# CAN.net
KiCad netlist of a schematic drawn in Altium Designer
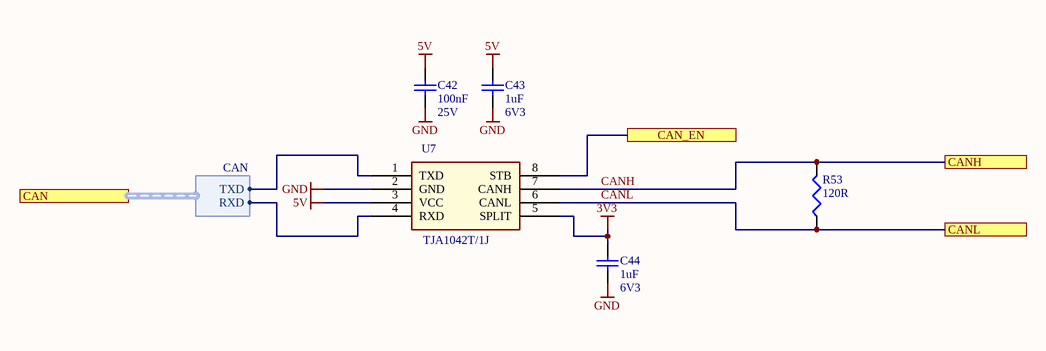
[diagram p0: CAN.SchDoc]

(export (version "E")
  (design (tool "Eeschema 10.0.6"))
  (components
    (comp (ref "C42")
      (value "100nF")
      (footprint "VESC_BMS:C0402")
      (description "Capacitor, 100nF, 25V, X7R")
      (fields (field (name "VOLTAGE RATING") "25V"))
      (libsource (lib "AR_Capacitors_Ceramic") (part "100nF/0402/CER/25V"))
    )
    (comp (ref "C43")
      (value "1uF")
      (footprint "VESC_BMS:C0402")
      (description "Capacitor, 1uF, 6.3V, X5R")
      (fields (field (name "VOLTAGE RATING") "6V3"))
      (libsource (lib "AR_Capacitors_Ceramic") (part "1uF/0402/CER/6.3V"))
    )
    (comp (ref "C44")
      (value "1uF")
      (footprint "VESC_BMS:C0402")
      (description "Capacitor, 1uF, 6.3V, X5R")
      (fields (field (name "VOLTAGE RATING") "6V3"))
      (libsource (lib "AR_Capacitors_Ceramic") (part "1uF/0402/CER/6.3V"))
    )
    (comp (ref "R53")
      (value "120R")
      (footprint "VESC_BMS:0805")
      (description "Resistor, 0R, 0.1%, 0.1W, 150V, 200PPM, 0805")
      (libsource (lib "VESC_BMS") (part "0/0805/0100W/150V_1"))
    )
    (comp (ref "U7")
      (value "TJA1042T/1J")
      (footprint "VESC_BMS:SOP-8")
      (libsource (lib "DB10005_DieBieMS") (part "TJA1042T/1J"))
    )
  )
  (nets
    (net (code "2") (name "/CANH") (class "Default")
      (node (ref "R53") (pin "2") (pinfunction "2_2") (pintype "passive"))
      (node (ref "U7") (pin "7") (pinfunction "CANH_7") (pintype "passive"))
    )
    (net (code "3") (name "/CANL") (class "Default")
      (node (ref "R53") (pin "1") (pinfunction "1_1") (pintype "passive"))
      (node (ref "U7") (pin "6") (pinfunction "CANL_6") (pintype "passive"))
    )
    (net (code "4") (name "/CAN_EN") (class "Default")
      (node (ref "U7") (pin "8") (pinfunction "STB_8") (pintype "passive"))
    )
    (net (code "5") (name "/RXD") (class "Default")
      (node (ref "U7") (pin "4") (pinfunction "RXD_4") (pintype "passive"))
    )
    (net (code "6") (name "/TXD") (class "Default")
      (node (ref "U7") (pin "1") (pinfunction "TXD_1") (pintype "passive"))
    )
    (net (code "8") (name "3V3") (class "Default")
      (node (ref "C44") (pin "2") (pinfunction "2_2") (pintype "passive"))
      (node (ref "U7") (pin "5") (pinfunction "SPLIT_5") (pintype "passive"))
    )
    (net (code "9") (name "5V") (class "Default")
      (node (ref "C42") (pin "2") (pinfunction "2_2") (pintype "passive"))
      (node (ref "C43") (pin "2") (pinfunction "2_2") (pintype "passive"))
      (node (ref "U7") (pin "3") (pinfunction "VCC_3") (pintype "passive"))
    )
    (net (code "10") (name "GND") (class "Default")
      (node (ref "C42") (pin "1") (pinfunction "1_1") (pintype "passive"))
      (node (ref "C43") (pin "1") (pinfunction "1_1") (pintype "passive"))
      (node (ref "C44") (pin "1") (pinfunction "1_1") (pintype "passive"))
      (node (ref "U7") (pin "2") (pinfunction "GND_2") (pintype "passive"))
    )
  )
)
